# power_schematic.net
KiCad netlist of a schematic drawn in Altium Designer
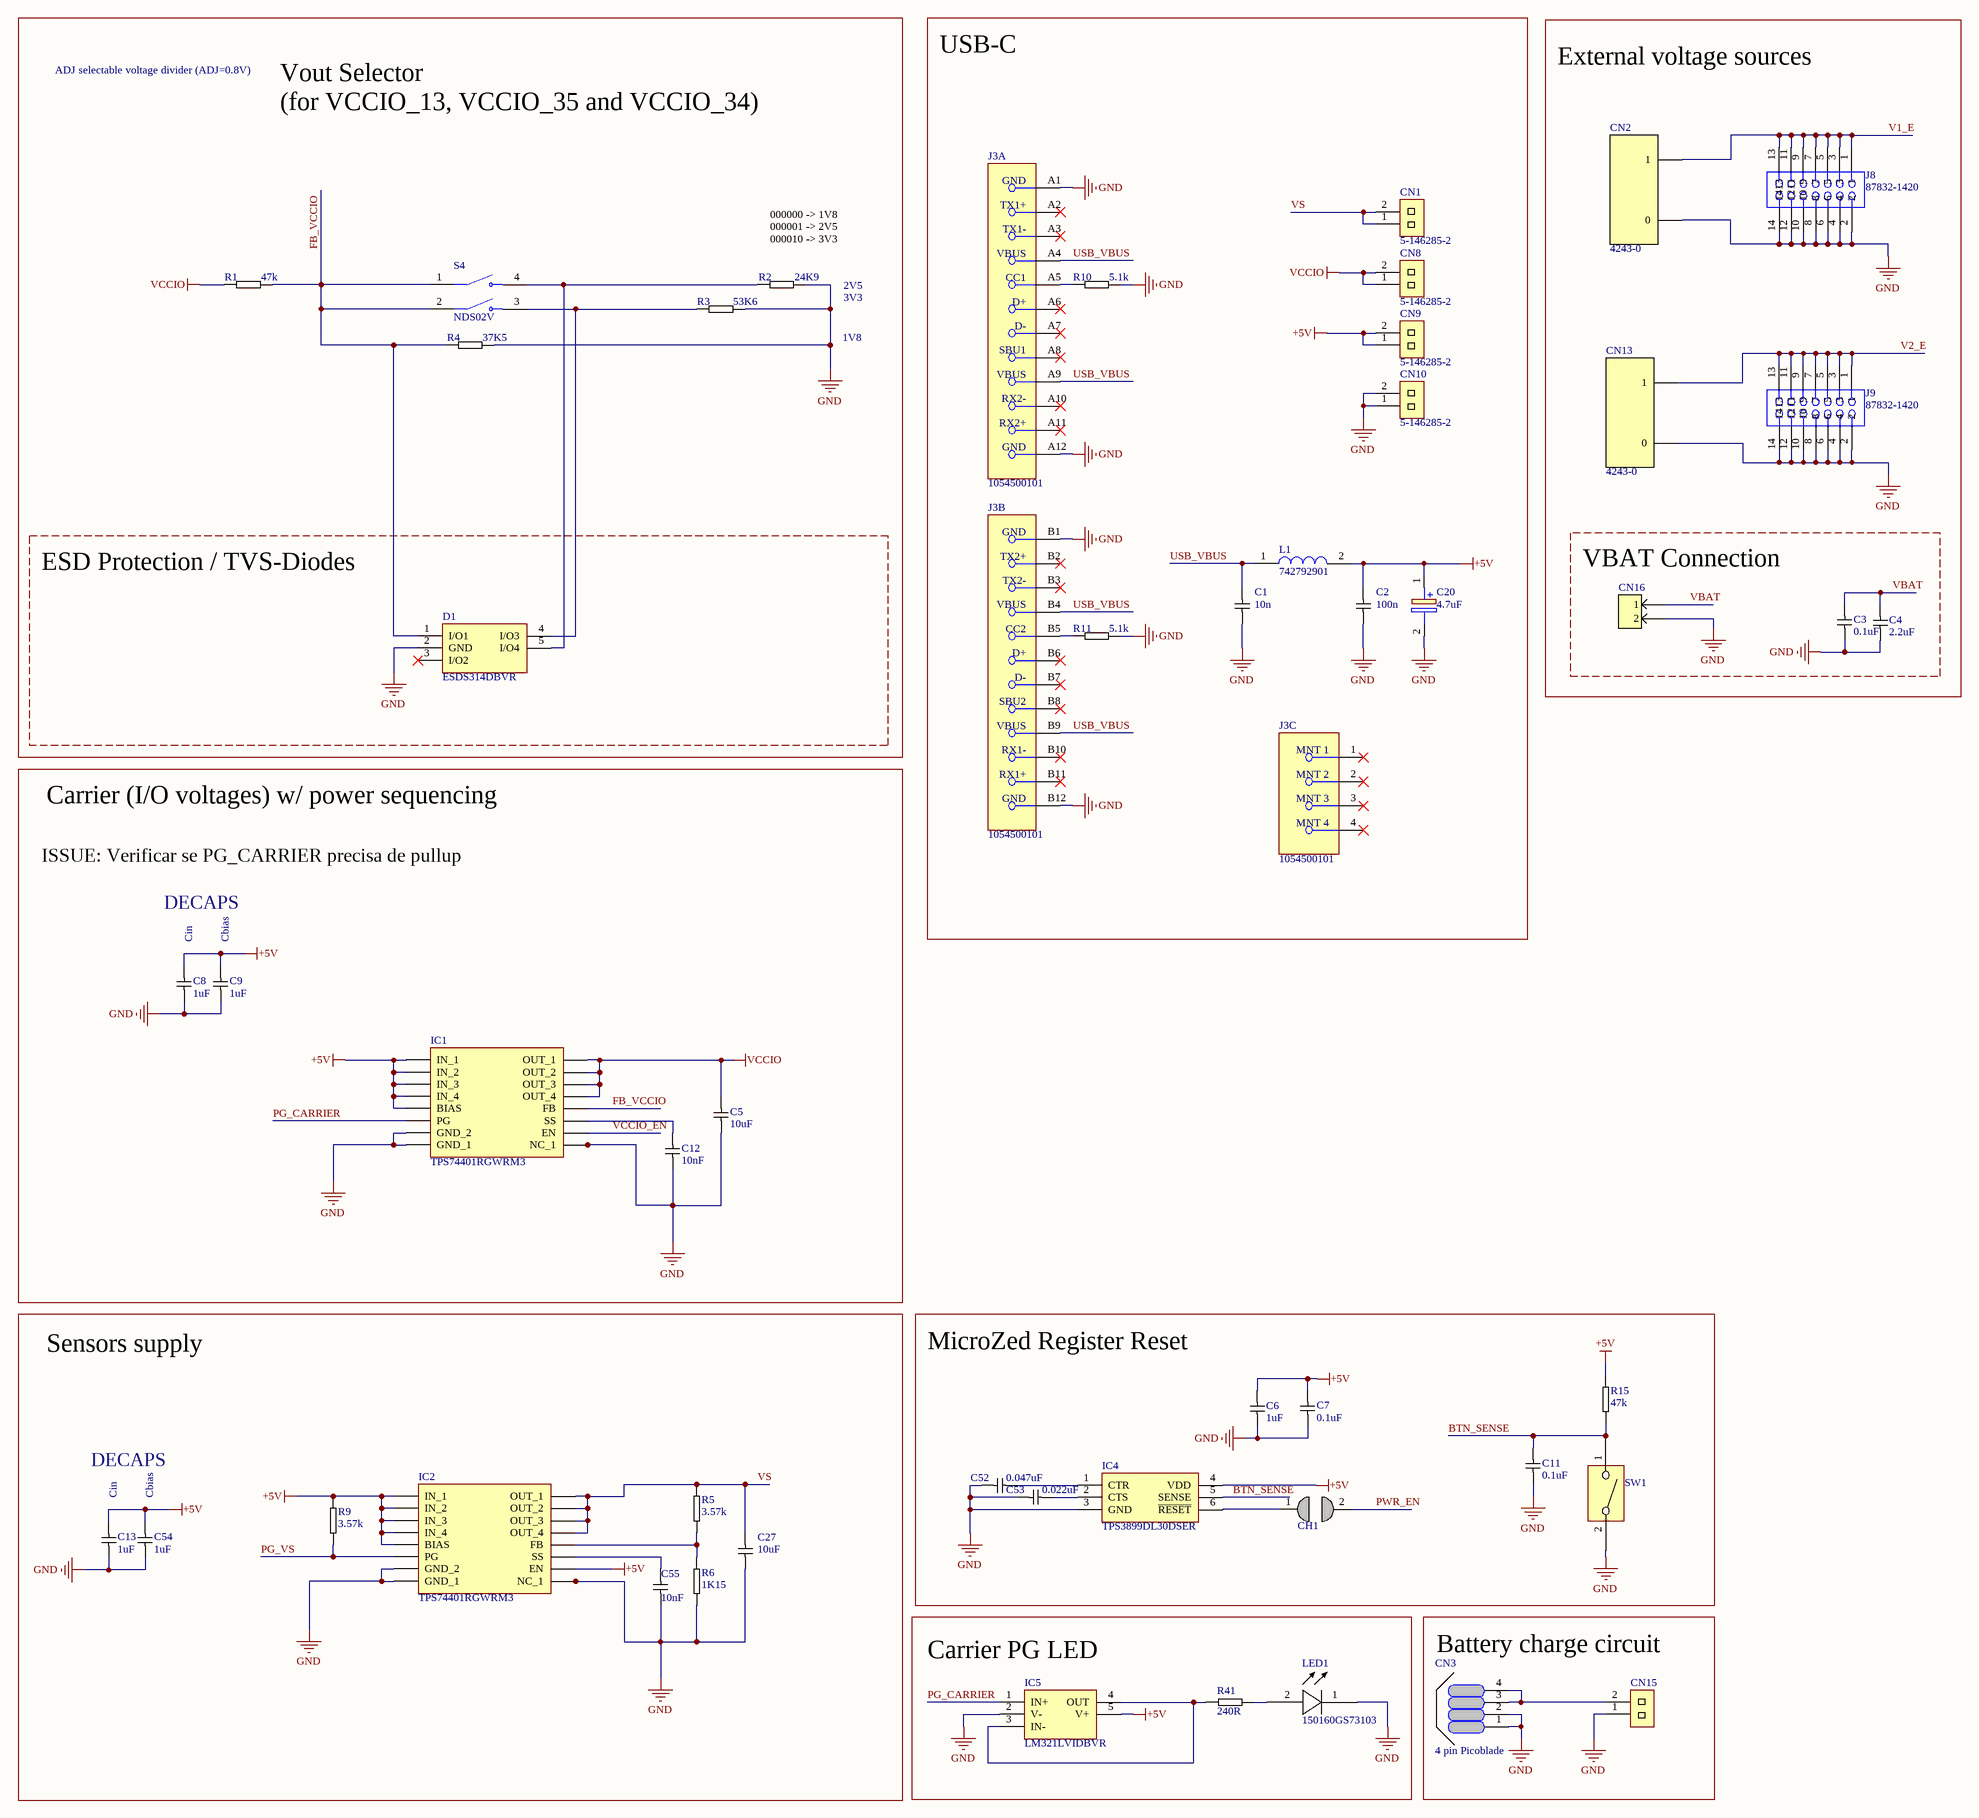
[diagram p0: power_schematic.SchDoc]

(export (version "E")
  (design (tool "Eeschema 10.0.6"))
  (components
    (comp (ref "C1")
      (value "10n")
      (footprint "C0603_MD")
      (description "CAP CER 10000PF 16V 10% X7R 0603")
      (fields (field (name "MANUFACTURER") "Murata") (field (name "VOLTAGE") "16V"))
      (libsource (lib "Capacitor") (part "GRM188R71C103KA01D"))
    )
    (comp (ref "C2")
      (value "100n")
      (footprint "C0603_MD")
      (description "CAP CER 0.1UF 25V X7R 0603")
      (fields
        (field (name "MANUFACTURER") "Samsung Electro-Mechanics America, Inc.")
        (field (name "VOLTAGE") "25V")
      )
      (libsource (lib "Capacitor") (part "CL10B104KA8NNNC"))
    )
    (comp (ref "C3")
      (value "0.1uF")
      (footprint "C0603_MD")
      (description "CAP CER 0.1UF 50V X7R 0603")
      (fields (field (name "MANUFACTURER") "Murata Electronics North America") (field (name "VOLTAGE") "50V"))
      (libsource (lib "Capacitor") (part "GRM188R71H104JA93D"))
    )
    (comp (ref "C4")
      (value "2.2uF")
      (footprint "C0603_MD")
      (description "CAP CER 2.2UF 16V X7R 0603")
      (fields (field (name "MANUFACTURER") "Taiyo Yuden") (field (name "VOLTAGE") "16V"))
      (libsource (lib "Capacitor") (part "EMK107BB7225MA-T"))
    )
    (comp (ref "C5")
      (value "10uF")
      (footprint "C0603_MD")
      (description "CAP CER 10UF 16V 20% X6S 0603")
      (fields (field (name "MANUFACTURER") "Murata Electronics North America") (field (name "VOLTAGE") "16V"))
      (libsource (lib "Capacitor") (part "GRM188C81C106MA73D"))
    )
    (comp (ref "C6")
      (value "1uF")
      (footprint "C0603_MD")
      (description "CAP CER 1UF 16V Y5V 0603")
      (fields (field (name "MANUFACTURER") "Taiyo Yuden") (field (name "VOLTAGE") "16V"))
      (libsource (lib "Capacitor") (part "EMK107F105ZA-T"))
    )
    (comp (ref "C7")
      (value "0.1uF")
      (footprint "C0603_MD")
      (description "CAP CER 0.1UF 25V X7R 0603")
      (fields
        (field (name "MANUFACTURER") "Samsung Electro-Mechanics America, Inc.")
        (field (name "VOLTAGE") "25V")
      )
      (libsource (lib "Capacitor") (part "CL10B104KA8NNNC"))
    )
    (comp (ref "C8")
      (value "Cin")
      (footprint "C0603_MD")
      (description "CAP CER 1UF 50V 10% X5R 0603")
      (fields
        (field (name "MANUFACTURER") "Taiyo Yuden")
        (field (name "VOLTAGE") "50V")
        (field (name "ALTIUM_VALUE") "1uF")
      )
      (libsource (lib "Capacitor") (part "UMK107BJ105KA-T"))
    )
    (comp (ref "C9")
      (value "Cbias")
      (footprint "C0603_MD")
      (description "CAP CER 1UF 50V 10% X5R 0603")
      (fields
        (field (name "MANUFACTURER") "Taiyo Yuden")
        (field (name "VOLTAGE") "50V")
        (field (name "ALTIUM_VALUE") "1uF")
      )
      (libsource (lib "Capacitor") (part "UMK107BJ105KA-T"))
    )
    (comp (ref "C11")
      (value "0.1uF")
      (footprint "C0603_MD")
      (description "CAP CER 0.1UF 25V X7R 0603")
      (fields
        (field (name "MANUFACTURER") "Samsung Electro-Mechanics America, Inc.")
        (field (name "VOLTAGE") "25V")
      )
      (libsource (lib "Capacitor") (part "CL10B104KA8NNNC"))
    )
    (comp (ref "C12")
      (value "10nF")
      (footprint "C0603_MD")
      (description "10000pF 50V Ceramic Capacitor X7R 0603")
      (fields
        (field (name "MANUFACTURER") "Samsung Electro-Mechanics America, Inc.")
        (field (name "VOLTAGE") "50V")
      )
      (libsource (lib "Capacitor") (part "CL10B103KB8NNNC"))
    )
    (comp (ref "C13")
      (value "Cin")
      (footprint "C0603_MD")
      (description "CAP CER 1UF 50V 10% X5R 0603")
      (fields
        (field (name "MANUFACTURER") "Taiyo Yuden")
        (field (name "VOLTAGE") "50V")
        (field (name "ALTIUM_VALUE") "1uF")
      )
      (libsource (lib "Capacitor") (part "UMK107BJ105KA-T"))
    )
    (comp (ref "C20")
      (value "4.7uF")
      (footprint "SamacSys:CAPAE660X770N")
      (description "Capacitor Polarised")
      (fields
        (field (name "MANUFACTURER_PART_NUMBER") "865080845004")
        (field (name "MOUSER PART NUMBER") "710-865080845004")
      )
      (libsource (lib "*") (part "865080845004"))
    )
    (comp (ref "C27")
      (value "10uF")
      (footprint "C0603_MD")
      (description "CAP CER 10UF 16V 20% X6S 0603")
      (fields (field (name "MANUFACTURER") "Murata Electronics North America") (field (name "VOLTAGE") "16V"))
      (libsource (lib "Capacitor") (part "GRM188C81C106MA73D"))
    )
    (comp (ref "C52")
      (value "0.047uF")
      (footprint "C0603_MD")
      (description "CAP CER 0.047UF 50V X7R 0603")
      (fields (field (name "MANUFACTURER") "Samsung Electro-Mechanics") (field (name "VOLTAGE") "50V"))
      (libsource (lib "Capacitor") (part "CL10B473KB8NNNC"))
    )
    (comp (ref "C53")
      (value "0.022uF")
      (footprint "C0603_MD")
      (description "CAP CER 0.022UF 50V X7R 0603")
      (fields
        (field (name "MANUFACTURER") "Samsung Electro-Mechanics America, Inc.")
        (field (name "VOLTAGE") "50V")
      )
      (libsource (lib "Capacitor") (part "CL10B223KB8NNNC"))
    )
    (comp (ref "C54")
      (value "Cbias")
      (footprint "C0603_MD")
      (description "CAP CER 1UF 50V 10% X5R 0603")
      (fields
        (field (name "MANUFACTURER") "Taiyo Yuden")
        (field (name "VOLTAGE") "50V")
        (field (name "ALTIUM_VALUE") "1uF")
      )
      (libsource (lib "Capacitor") (part "UMK107BJ105KA-T"))
    )
    (comp (ref "C55")
      (value "10nF")
      (footprint "C0603_MD")
      (description "10000pF 50V Ceramic Capacitor X7R 0603")
      (fields
        (field (name "MANUFACTURER") "Samsung Electro-Mechanics America, Inc.")
        (field (name "VOLTAGE") "50V")
      )
      (libsource (lib "Capacitor") (part "CL10B103KB8NNNC"))
    )
    (comp (ref "CH1")
      (value "Solder Jumper")
      (footprint "Solder Jumper")
      (description "PCB Solder jumper")
      (libsource (lib "Miscellaneous") (part "Solder Jumper"))
    )
    (comp (ref "CN1")
      (value "5-146285-2")
      (footprint "PIN BAR 2 2.54mm 180 GRAUS")
      (description "02 MODII HDR SRST B/A .100CL")
      (fields (field (name "MANUFACTURER") "TE Connectivity"))
      (libsource (lib "Connector") (part "5-146285-2"))
    )
    (comp (ref "CN2")
      (value "4243-0")
      (footprint "4243-0")
      (description "POMONA, 4243-0, Binding Post, 4243 Series, 15 A, 60 VDC, Tin Plated Contacts, Brass, Black")
      (fields (field (name "MANUFACTURER") "Pomona Electronics"))
      (libsource (lib "flatsat_platform_2") (part "4243-0"))
    )
    (comp (ref "CN3")
      (value "4 pin Picoblade")
      (footprint "PICO BLADE 0532610471")
      (description "1.25mm Pitch PicoBlade™ Header, Surface Mount, Vertical, 4 Circuits")
      (fields (field (name "MANUFACTURER") "Molex") (field (name "MANUFACTURER PART NUMBER") "53398-0471"))
      (libsource (lib "flatsat_platform_2") (part "0533980471"))
    )
    (comp (ref "CN8")
      (value "5-146285-2")
      (footprint "PIN BAR 2 2.54mm 180 GRAUS")
      (description "02 MODII HDR SRST B/A .100CL")
      (fields (field (name "MANUFACTURER") "TE Connectivity"))
      (libsource (lib "Connector") (part "5-146285-2"))
    )
    (comp (ref "CN9")
      (value "5-146285-2")
      (footprint "PIN BAR 2 2.54mm 180 GRAUS")
      (description "02 MODII HDR SRST B/A .100CL")
      (fields (field (name "MANUFACTURER") "TE Connectivity"))
      (libsource (lib "Connector") (part "5-146285-2"))
    )
    (comp (ref "CN10")
      (value "5-146285-2")
      (footprint "PIN BAR 2 2.54mm 180 GRAUS")
      (description "02 MODII HDR SRST B/A .100CL")
      (fields (field (name "MANUFACTURER") "TE Connectivity"))
      (libsource (lib "Connector") (part "5-146285-2"))
    )
    (comp (ref "CN13")
      (value "4243-0")
      (footprint "4243-0")
      (description "POMONA, 4243-0, Binding Post, 4243 Series, 15 A, 60 VDC, Tin Plated Contacts, Brass, Black")
      (fields (field (name "MANUFACTURER") "Pomona Electronics"))
      (libsource (lib "flatsat_platform_2") (part "4243-0"))
    )
    (comp (ref "CN15")
      (value "JST 2 position header 2.5mm")
      (footprint "B2B-XH-A-M(LF)(SN)")
      (description "CONN HEADER TOP 2POS 2.5MM GRN")
      (fields (field (name "MANUFACTURER") "TE Connectivity"))
      (libsource (lib "Connector") (part "5-146285-2"))
    )
    (comp (ref "CN16")
      (value "JST 2 position header 2.5mm")
      (footprint "B2B-XH-A-M(LF)(SN)")
      (description "CONN HEADER TOP 2POS 2.5MM GRN")
      (fields
        (field (name "MANUFACTURER") "JST")
        (field (name "MANUFACTURER PART NUMBER") "B2B-XH-A-M(LF)(SN)")
      )
      (libsource (lib "flatsat_platform_2") (part "B2B-XH-A-M(LF)(SN)"))
    )
    (comp (ref "D1")
      (value "ESDS314DBVR")
      (footprint "flatsat_platform_2:SOT95P280X145-5N")
      (description "Diode")
      (fields (field (name "MOUSER PART NUMBER") "595-ESDS314DBVR"))
      (libsource (lib "*") (part "ESDS314DBVR"))
    )
    (comp (ref "IC1")
      (value "TPS74401RGWRM3")
      (footprint "SamacSys:QFN65P500X500X100-21N-D")
      (description "Integrated Circuit")
      (fields (field (name "MOUSER PART NUMBER") "595-TPS74401RGWRM3"))
      (libsource (lib "SamacSys") (part "TPS74401RGWRM3"))
    )
    (comp (ref "IC2")
      (value "TPS74401RGWRM3")
      (footprint "SamacSys:QFN65P500X500X100-21N-D")
      (description "Integrated Circuit")
      (fields (field (name "MOUSER PART NUMBER") "595-TPS74401RGWRM3"))
      (libsource (lib "SamacSys") (part "TPS74401RGWRM3"))
    )
    (comp (ref "IC4")
      (value "TPS3899DL30DSER")
      (footprint "flatsat_platform_2:TPS3899DL30DSER")
      (description "Integrated Circuit")
      (fields (field (name "MOUSER PART NUMBER") "595-TPS3899DL30DSER"))
      (libsource (lib "*") (part "TPS3899DL30DSER"))
    )
    (comp (ref "IC5")
      (value "LM321LVIDBVR")
      (footprint "flatsat_platform_2:SOT95P280X145-5N")
      (description "Integrated Circuit")
      (fields (field (name "MOUSER PART NUMBER") "595-LM321LVIDBVR"))
      (libsource (lib "*") (part "LM321LVIDBVR"))
    )
    (comp (ref "J3")
      (value "1054500101")
      (footprint "FP-1054500101-MFG")
      (description "CONN RCP USB3.1 TYPEC 24P SMD RA")
      (fields
        (field (name "MANUFACTURER") "Molex")
        (field (name "OCTOPART") "https://octopart.com/105450-0101-molex-68082325")
      )
      (libsource (lib "Altium Content Vault") (part "9808b19ecaf079fb99eed69f0495cd0"))
    )
    (comp (ref "J8")
      (value "87832-1420")
      (footprint "SAMTEC_TSW-107-05-F-D")
      (description "Connector Header Surface Mount 14 position 0.079 _2.00mm_")
      (fields (field (name "MF") "Molex") (field (name "MANUFACTURER PART NUMBER") "TSW-107-05-F-D"))
      (libsource (lib "flatsat_platform_2") (part "87832-1420"))
    )
    (comp (ref "J9")
      (value "87832-1420")
      (footprint "SAMTEC_TSW-107-05-F-D")
      (description "Connector Header Surface Mount 14 position 0.079 _2.00mm_")
      (fields (field (name "MF") "Molex") (field (name "MANUFACTURER PART NUMBER") "TSW-107-05-F-D"))
      (libsource (lib "flatsat_platform_2") (part "87832-1420"))
    )
    (comp (ref "L1")
      (value "742792901")
      (footprint "SamacSys:WE-PF_7427929...60")
      (description "Inductor")
      (fields (field (name "MOUSER PART NUMBER") "710-742792901"))
      (libsource (lib "SamacSys") (part "742792901"))
    )
    (comp (ref "LED1")
      (value "150160GS73103")
      (footprint "0603 (1608 metric)")
      (libsource (lib "flatsat_platform_2") (part "150160GS73103"))
    )
    (comp (ref "R1")
      (value "47k")
      (footprint "R0603_HD")
      (description "RES 47K OHM 1/10W 1% 0603")
      (fields (field (name "MANUFACTURER") "Stackpole Electronics Inc") (field (name "TOLERANCE") "1%"))
      (libsource (lib "Resistor") (part "RMCF0603FT47K0"))
    )
    (comp (ref "R2")
      (value "24K9")
      (footprint "R0603_HD")
      (description "Resistor")
      (fields
        (field (name "MANUFACTURER_PART_NUMBER") "ERJ-PB3B2492V")
        (field (name "MOUSER PART NUMBER") "667-ERJ-PB3B2492V")
      )
      (libsource (lib "SamacSys") (part "ERJ-PB3B2492V"))
    )
    (comp (ref "R3")
      (value "53K6")
      (footprint "R0603_HD")
      (description "Resistor")
      (fields (field (name "MANUFACTURER_PART_NUMBER") "ERJH3ED3652V"))
      (libsource (lib "SamacSys") (part "ERJH3ED3652V"))
    )
    (comp (ref "R4")
      (value "37K5")
      (footprint "R0603_HD")
      (description "Resistor")
      (fields (field (name "MANUFACTURER_PART_NUMBER") "ERJ-H3ED3652V"))
      (libsource (lib "SamacSys") (part "ERJ-H3ED3652V"))
    )
    (comp (ref "R5")
      (value "3.57k")
      (footprint "R0603_MD")
      (description "RES 3.57K OHM 1/10W 1% 0603")
      (fields (field (name "MANUFACTURER") "Stackpole Electronics Inc") (field (name "TOLERANCE") "1%"))
      (libsource (lib "Resistor") (part "RMCF0603FT3K57"))
    )
    (comp (ref "R6")
      (value "1K15")
      (footprint "R0603_MD")
      (description "Resistor")
      (fields
        (field (name "MANUFACTURER_PART_NUMBER") "CPF0603F1K15C1")
        (field (name "MOUSER PART NUMBER") "279-CPF0603F1K15C1")
      )
      (libsource (lib "SamacSys") (part "CPF0603F1K15C1"))
    )
    (comp (ref "R9")
      (value "3.57k")
      (footprint "R0603_MD")
      (description "RES 3.57K OHM 1/10W 1% 0603")
      (fields (field (name "MANUFACTURER") "Stackpole Electronics Inc") (field (name "TOLERANCE") "1%"))
      (libsource (lib "Resistor") (part "RMCF0603FT3K57"))
    )
    (comp (ref "R10")
      (value "5.1k")
      (footprint "R0603_MD")
      (description "RES 5.1K OHM 1/10W 1% 0603")
      (fields (field (name "MANUFACTURER") "Stackpole Electronics Inc") (field (name "TOLERANCE") "1%"))
      (libsource (lib "Resistor") (part "RMCF0603FT5K10"))
    )
    (comp (ref "R11")
      (value "5.1k")
      (footprint "R0603_MD")
      (description "RES 5.1K OHM 1/10W 1% 0603")
      (fields (field (name "MANUFACTURER") "Stackpole Electronics Inc") (field (name "TOLERANCE") "1%"))
      (libsource (lib "Resistor") (part "RMCF0603FT5K10"))
    )
    (comp (ref "R15")
      (value "47k")
      (footprint "R0603_MD")
      (description "RES 47K OHM 1/10W 1% 0603")
      (fields (field (name "MANUFACTURER") "Stackpole Electronics Inc") (field (name "TOLERANCE") "1%"))
      (libsource (lib "Resistor") (part "RMCF0603FT47K0"))
    )
    (comp (ref "R41")
      (value "240R")
      (footprint "R0603_MD")
      (description "RES SMD 240 OHM 1% 1/10W 0603")
      (fields (field (name "MANUFACTURER") "Yageo") (field (name "TOLERANCE") "1%"))
      (libsource (lib "Resistor") (part "RC0603FR-07240RL"))
    )
    (comp (ref "S4")
      (value "NDS02V")
      (footprint "SamacSys:NDS02V")
      (description "Switch")
      (fields (field (name "MOUSER PART NUMBER") "642-NDS02V"))
      (libsource (lib "SamacSys") (part "NDS02V"))
    )
    (comp (ref "SW1")
      (value "434123050836")
      (footprint "4341x30508x6")
      (description "SWITCH TACTILE SPST-NO 0.05A 12V")
      (fields (field (name "MANUFACTURER") "Wurth Electronics Inc."))
      (libsource (lib "Switch") (part "434123050836"))
    )
  )
  (nets
    (net (code "1") (name "+5V") (class "Default")
      (node (ref "C13") (pin "1") (pinfunction "1_1") (pintype "passive"))
      (node (ref "C2") (pin "1") (pinfunction "1_1") (pintype "passive"))
      (node (ref "C20") (pin "1") (pinfunction "+_1") (pintype "passive"))
      (node (ref "C54") (pin "1") (pinfunction "1_1") (pintype "passive"))
      (node (ref "C6") (pin "1") (pinfunction "1_1") (pintype "passive"))
      (node (ref "C7") (pin "1") (pinfunction "1_1") (pintype "passive"))
      (node (ref "C8") (pin "1") (pinfunction "1_1") (pintype "passive"))
      (node (ref "C9") (pin "1") (pinfunction "1_1") (pintype "passive"))
      (node (ref "CN9") (pin "1") (pinfunction "1_1") (pintype "passive"))
      (node (ref "CN9") (pin "2") (pinfunction "2_2") (pintype "passive"))
      (node (ref "IC1") (pin "10") (pinfunction "BIAS_10") (pintype "passive"))
      (node (ref "IC1") (pin "5") (pinfunction "IN_1_5") (pintype "passive"))
      (node (ref "IC1") (pin "6") (pinfunction "IN_2_6") (pintype "passive"))
      (node (ref "IC1") (pin "7") (pinfunction "IN_3_7") (pintype "passive"))
      (node (ref "IC1") (pin "8") (pinfunction "IN_4_8") (pintype "passive"))
      (node (ref "IC2") (pin "10") (pinfunction "BIAS_10") (pintype "passive"))
      (node (ref "IC2") (pin "11") (pinfunction "EN_11") (pintype "passive"))
      (node (ref "IC2") (pin "5") (pinfunction "IN_1_5") (pintype "passive"))
      (node (ref "IC2") (pin "6") (pinfunction "IN_2_6") (pintype "passive"))
      (node (ref "IC2") (pin "7") (pinfunction "IN_3_7") (pintype "passive"))
      (node (ref "IC2") (pin "8") (pinfunction "IN_4_8") (pintype "passive"))
      (node (ref "IC4") (pin "4") (pinfunction "VDD_4") (pintype "passive"))
      (node (ref "IC5") (pin "5") (pinfunction "V+_5") (pintype "passive"))
      (node (ref "L1") (pin "2") (pinfunction "2_2") (pintype "passive"))
      (node (ref "R15") (pin "1") (pinfunction "1_1") (pintype "passive"))
      (node (ref "R9") (pin "1") (pinfunction "1_1") (pintype "passive"))
    )
    (net (code "2") (name "/BTN_SENSE") (class "Default")
      (node (ref "C11") (pin "2") (pinfunction "2_2") (pintype "passive"))
      (node (ref "IC4") (pin "5") (pinfunction "SENSE_5") (pintype "passive"))
      (node (ref "R15") (pin "2") (pinfunction "2_2") (pintype "passive"))
      (node (ref "SW1") (pin "1") (pinfunction "NC_1") (pintype "passive"))
    )
    (net (code "3") (name "/FB_VCCIO") (class "Default")
      (node (ref "D1") (pin "1") (pinfunction "I/O1_1") (pintype "passive"))
      (node (ref "IC1") (pin "16") (pinfunction "FB_16") (pintype "passive"))
      (node (ref "R1") (pin "2") (pinfunction "2_2") (pintype "passive"))
      (node (ref "R4") (pin "1") (pinfunction "1_1") (pintype "passive"))
      (node (ref "S4") (pin "1") (pinfunction "COM_1_1") (pintype "passive"))
      (node (ref "S4") (pin "2") (pinfunction "COM_2_2") (pintype "passive"))
    )
    (net (code "4") (name "/PG_CARRIER") (class "Default")
      (node (ref "IC1") (pin "9") (pinfunction "PG_9") (pintype "passive"))
      (node (ref "IC5") (pin "1") (pinfunction "IN+_1") (pintype "passive"))
    )
    (net (code "5") (name "/PG_VS") (class "Default")
      (node (ref "IC2") (pin "9") (pinfunction "PG_9") (pintype "passive"))
      (node (ref "R9") (pin "2") (pinfunction "2_2") (pintype "passive"))
    )
    (net (code "6") (name "/PWR_EN") (class "Default")
      (node (ref "CH1") (pin "2") (pinfunction "C_2") (pintype "passive"))
    )
    (net (code "7") (name "/USB_VBUS") (class "Default")
      (node (ref "C1") (pin "1") (pinfunction "1_1") (pintype "passive"))
      (node (ref "J3") (pin "A4") (pinfunction "VBUS_A4") (pintype "passive"))
      (node (ref "J3") (pin "A9") (pinfunction "VBUS_A9") (pintype "passive"))
      (node (ref "J3") (pin "B4") (pinfunction "VBUS_B4") (pintype "passive"))
      (node (ref "J3") (pin "B9") (pinfunction "VBUS_B9") (pintype "passive"))
      (node (ref "L1") (pin "1") (pinfunction "1_1") (pintype "passive"))
    )
    (net (code "8") (name "/V1_E") (class "Default")
      (node (ref "CN2") (pin "1") (pinfunction "1_1") (pintype "passive"))
      (node (ref "J8") (pin "1") (pinfunction "1_1") (pintype "passive"))
      (node (ref "J8") (pin "11") (pinfunction "11_11") (pintype "passive"))
      (node (ref "J8") (pin "13") (pinfunction "13_13") (pintype "passive"))
      (node (ref "J8") (pin "3") (pinfunction "3_3") (pintype "passive"))
      (node (ref "J8") (pin "5") (pinfunction "5_5") (pintype "passive"))
      (node (ref "J8") (pin "7") (pinfunction "7_7") (pintype "passive"))
      (node (ref "J8") (pin "9") (pinfunction "9_9") (pintype "passive"))
    )
    (net (code "9") (name "/V2_E") (class "Default")
      (node (ref "CN13") (pin "1") (pinfunction "1_1") (pintype "passive"))
      (node (ref "J9") (pin "1") (pinfunction "1_1") (pintype "passive"))
      (node (ref "J9") (pin "11") (pinfunction "11_11") (pintype "passive"))
      (node (ref "J9") (pin "13") (pinfunction "13_13") (pintype "passive"))
      (node (ref "J9") (pin "3") (pinfunction "3_3") (pintype "passive"))
      (node (ref "J9") (pin "5") (pinfunction "5_5") (pintype "passive"))
      (node (ref "J9") (pin "7") (pinfunction "7_7") (pintype "passive"))
      (node (ref "J9") (pin "9") (pinfunction "9_9") (pintype "passive"))
    )
    (net (code "10") (name "/VBAT") (class "Default")
      (node (ref "C3") (pin "1") (pinfunction "1_1") (pintype "passive"))
      (node (ref "C4") (pin "1") (pinfunction "1_1") (pintype "passive"))
      (node (ref "CN16") (pin "1") (pinfunction "1_1") (pintype "passive"))
    )
    (net (code "11") (name "/VCCIO_EN") (class "Default")
      (node (ref "IC1") (pin "11") (pinfunction "EN_11") (pintype "passive"))
    )
    (net (code "12") (name "/VS") (class "Default")
      (node (ref "C27") (pin "1") (pinfunction "1_1") (pintype "passive"))
      (node (ref "CN1") (pin "1") (pinfunction "1_1") (pintype "passive"))
      (node (ref "CN1") (pin "2") (pinfunction "2_2") (pintype "passive"))
      (node (ref "IC2") (pin "1") (pinfunction "OUT_1_1") (pintype "passive"))
      (node (ref "IC2") (pin "18") (pinfunction "OUT_2_18") (pintype "passive"))
      (node (ref "IC2") (pin "19") (pinfunction "OUT_3_19") (pintype "passive"))
      (node (ref "IC2") (pin "20") (pinfunction "OUT_4_20") (pintype "passive"))
      (node (ref "R5") (pin "1") (pinfunction "1_1") (pintype "passive"))
    )
    (net (code "13") (name "GND") (class "Default")
      (node (ref "C1") (pin "2") (pinfunction "2_2") (pintype "passive"))
      (node (ref "C11") (pin "1") (pinfunction "1_1") (pintype "passive"))
      (node (ref "C12") (pin "2") (pinfunction "2_2") (pintype "passive"))
      (node (ref "C13") (pin "2") (pinfunction "2_2") (pintype "passive"))
      (node (ref "C2") (pin "2") (pinfunction "2_2") (pintype "passive"))
      (node (ref "C20") (pin "2") (pinfunction "-_2") (pintype "passive"))
      (node (ref "C27") (pin "2") (pinfunction "2_2") (pintype "passive"))
      (node (ref "C3") (pin "2") (pinfunction "2_2") (pintype "passive"))
      (node (ref "C4") (pin "2") (pinfunction "2_2") (pintype "passive"))
      (node (ref "C5") (pin "2") (pinfunction "2_2") (pintype "passive"))
      (node (ref "C52") (pin "2") (pinfunction "2_2") (pintype "passive"))
      (node (ref "C53") (pin "2") (pinfunction "2_2") (pintype "passive"))
      (node (ref "C54") (pin "2") (pinfunction "2_2") (pintype "passive"))
      (node (ref "C55") (pin "1") (pinfunction "1_1") (pintype "passive"))
      (node (ref "C6") (pin "2") (pinfunction "2_2") (pintype "passive"))
      (node (ref "C7") (pin "2") (pinfunction "2_2") (pintype "passive"))
      (node (ref "C8") (pin "2") (pinfunction "2_2") (pintype "passive"))
      (node (ref "C9") (pin "2") (pinfunction "2_2") (pintype "passive"))
      (node (ref "CN10") (pin "1") (pinfunction "1_1") (pintype "passive"))
      (node (ref "CN10") (pin "2") (pinfunction "2_2") (pintype "passive"))
      (node (ref "CN13") (pin "0") (pinfunction "0_0") (pintype "passive"))
      (node (ref "CN15") (pin "1") (pinfunction "1_1") (pintype "passive"))
      (node (ref "CN16") (pin "2") (pinfunction "2_2") (pintype "passive"))
      (node (ref "CN2") (pin "0") (pinfunction "0_0") (pintype "passive"))
      (node (ref "CN3") (pin "1") (pinfunction "1_1") (pintype "passive"))
      (node (ref "CN3") (pin "2") (pinfunction "2_2") (pintype "passive"))
      (node (ref "D1") (pin "2") (pinfunction "GND_2") (pintype "passive"))
      (node (ref "IC1") (pin "12") (pinfunction "GND_1_12") (pintype "passive"))
      (node (ref "IC1") (pin "13") (pinfunction "NC_4_13") (pintype "passive"))
      (node (ref "IC1") (pin "14") (pinfunction "NC_5_14") (pintype "passive"))
      (node (ref "IC1") (pin "17") (pinfunction "NC_6_17") (pintype "passive"))
      (node (ref "IC1") (pin "2") (pinfunction "NC_1_2") (pintype "passive"))
      (node (ref "IC1") (pin "21") (pinfunction "GND_2_21") (pintype "passive"))
      (node (ref "IC1") (pin "3") (pinfunction "NC_2_3") (pintype "passive"))
      (node (ref "IC1") (pin "4") (pinfunction "NC_3_4") (pintype "passive"))
      (node (ref "IC2") (pin "12") (pinfunction "GND_1_12") (pintype "passive"))
      (node (ref "IC2") (pin "13") (pinfunction "NC_4_13") (pintype "passive"))
      (node (ref "IC2") (pin "14") (pinfunction "NC_5_14") (pintype "passive"))
      (node (ref "IC2") (pin "17") (pinfunction "NC_6_17") (pintype "passive"))
      (node (ref "IC2") (pin "2") (pinfunction "NC_1_2") (pintype "passive"))
      (node (ref "IC2") (pin "21") (pinfunction "GND_2_21") (pintype "passive"))
      (node (ref "IC2") (pin "3") (pinfunction "NC_2_3") (pintype "passive"))
      (node (ref "IC2") (pin "4") (pinfunction "NC_3_4") (pintype "passive"))
      (node (ref "IC4") (pin "3") (pinfunction "GND_3") (pintype "passive"))
      (node (ref "IC5") (pin "2") (pinfunction "V-_2") (pintype "passive"))
      (node (ref "J3") (pin "A1") (pinfunction "GND_A1") (pintype "passive"))
      (node (ref "J3") (pin "A12") (pinfunction "GND_A12") (pintype "passive"))
      (node (ref "J3") (pin "B1") (pinfunction "GND_B1") (pintype "passive"))
      (node (ref "J3") (pin "B12") (pinfunction "GND_B12") (pintype "passive"))
      (node (ref "J8") (pin "10") (pinfunction "10_10") (pintype "passive"))
      (node (ref "J8") (pin "12") (pinfunction "12_12") (pintype "passive"))
      (node (ref "J8") (pin "14") (pinfunction "14_14") (pintype "passive"))
      (node (ref "J8") (pin "2") (pinfunction "2_2") (pintype "passive"))
      (node (ref "J8") (pin "4") (pinfunction "4_4") (pintype "passive"))
      (node (ref "J8") (pin "6") (pinfunction "6_6") (pintype "passive"))
      (node (ref "J8") (pin "8") (pinfunction "8_8") (pintype "passive"))
      (node (ref "J9") (pin "10") (pinfunction "10_10") (pintype "passive"))
      (node (ref "J9") (pin "12") (pinfunction "12_12") (pintype "passive"))
      (node (ref "J9") (pin "14") (pinfunction "14_14") (pintype "passive"))
      (node (ref "J9") (pin "2") (pinfunction "2_2") (pintype "passive"))
      (node (ref "J9") (pin "4") (pinfunction "4_4") (pintype "passive"))
      (node (ref "J9") (pin "6") (pinfunction "6_6") (pintype "passive"))
      (node (ref "J9") (pin "8") (pinfunction "8_8") (pintype "passive"))
      (node (ref "LED1") (pin "1") (pinfunction "Cathode_1") (pintype "passive"))
      (node (ref "R10") (pin "2") (pinfunction "2_2") (pintype "passive"))
      (node (ref "R11") (pin "2") (pinfunction "2_2") (pintype "passive"))
      (node (ref "R2") (pin "2") (pinfunction "2_2") (pintype "passive"))
      (node (ref "R3") (pin "2") (pinfunction "2_2") (pintype "passive"))
      (node (ref "R4") (pin "2") (pinfunction "2_2") (pintype "passive"))
      (node (ref "R6") (pin "2") (pinfunction "2_2") (pintype "passive"))
      (node (ref "SW1") (pin "2") (pinfunction "C_2") (pintype "passive"))
    )
    (net (code "14") (name "Net-(CH1-NC)") (class "Default")
      (node (ref "CH1") (pin "1") (pinfunction "NC_1") (pintype "passive"))
      (node (ref "IC4") (pin "6") (pinfunction "~{RESET}_6") (pintype "passive"))
    )
    (net (code "15") (name "Net-(CN15-Pad2)") (class "Default")
      (node (ref "CN15") (pin "2") (pinfunction "2_2") (pintype "passive"))
      (node (ref "CN3") (pin "3") (pinfunction "3_3") (pintype "passive"))
      (node (ref "CN3") (pin "4") (pinfunction "4_4") (pintype "passive"))
    )
    (net (code "16") (name "Net-(D1-I{slash}O3)") (class "Default")
      (node (ref "D1") (pin "4") (pinfunction "I/O3_4") (pintype "passive"))
      (node (ref "R3") (pin "1") (pinfunction "1_1") (pintype "passive"))
      (node (ref "S4") (pin "3") (pinfunction "NO_1_3") (pintype "passive"))
    )
    (net (code "17") (name "Net-(D1-I{slash}O4)") (class "Default")
      (node (ref "D1") (pin "5") (pinfunction "I/O4_5") (pintype "passive"))
      (node (ref "R2") (pin "1") (pinfunction "1_1") (pintype "passive"))
      (node (ref "S4") (pin "4") (pinfunction "NO_2_4") (pintype "passive"))
    )
    (net (code "18") (name "Net-(IC1-SS)") (class "Default")
      (node (ref "C12") (pin "1") (pinfunction "1_1") (pintype "passive"))
      (node (ref "IC1") (pin "15") (pinfunction "SS_15") (pintype "passive"))
    )
    (net (code "19") (name "Net-(IC2-FB)") (class "Default")
      (node (ref "IC2") (pin "16") (pinfunction "FB_16") (pintype "passive"))
      (node (ref "R5") (pin "2") (pinfunction "2_2") (pintype "passive"))
      (node (ref "R6") (pin "1") (pinfunction "1_1") (pintype "passive"))
    )
    (net (code "20") (name "Net-(IC2-SS)") (class "Default")
      (node (ref "C55") (pin "2") (pinfunction "2_2") (pintype "passive"))
      (node (ref "IC2") (pin "15") (pinfunction "SS_15") (pintype "passive"))
    )
    (net (code "21") (name "Net-(IC4-CTR)") (class "Default")
      (node (ref "C52") (pin "1") (pinfunction "1_1") (pintype "passive"))
      (node (ref "IC4") (pin "1") (pinfunction "CTR_1") (pintype "passive"))
    )
    (net (code "22") (name "Net-(IC4-CTS)") (class "Default")
      (node (ref "C53") (pin "1") (pinfunction "1_1") (pintype "passive"))
      (node (ref "IC4") (pin "2") (pinfunction "CTS_2") (pintype "passive"))
    )
    (net (code "23") (name "Net-(IC5-IN-)") (class "Default")
      (node (ref "IC5") (pin "3") (pinfunction "IN-_3") (pintype "passive"))
      (node (ref "IC5") (pin "4") (pinfunction "OUT_4") (pintype "passive"))
      (node (ref "R41") (pin "1") (pinfunction "1_1") (pintype "passive"))
    )
    (net (code "24") (name "Net-(J3A-CC1)") (class "Default")
      (node (ref "J3") (pin "A5") (pinfunction "CC1_A5") (pintype "passive"))
      (node (ref "R10") (pin "1") (pinfunction "1_1") (pintype "passive"))
    )
    (net (code "25") (name "Net-(J3B-CC2)") (class "Default")
      (node (ref "J3") (pin "B5") (pinfunction "CC2_B5") (pintype "passive"))
      (node (ref "R11") (pin "1") (pinfunction "1_1") (pintype "passive"))
    )
    (net (code "26") (name "Net-(LED1-anode)") (class "Default")
      (node (ref "LED1") (pin "2") (pinfunction "anode_2") (pintype "passive"))
      (node (ref "R41") (pin "2") (pinfunction "2_2") (pintype "passive"))
    )
    (net (code "27") (name "VCCIO") (class "Default")
      (node (ref "C5") (pin "1") (pinfunction "1_1") (pintype "passive"))
      (node (ref "CN8") (pin "1") (pinfunction "1_1") (pintype "passive"))
      (node (ref "CN8") (pin "2") (pinfunction "2_2") (pintype "passive"))
      (node (ref "IC1") (pin "1") (pinfunction "OUT_1_1") (pintype "passive"))
      (node (ref "IC1") (pin "18") (pinfunction "OUT_2_18") (pintype "passive"))
      (node (ref "IC1") (pin "19") (pinfunction "OUT_3_19") (pintype "passive"))
      (node (ref "IC1") (pin "20") (pinfunction "OUT_4_20") (pintype "passive"))
      (node (ref "R1") (pin "1") (pinfunction "1_1") (pintype "passive"))
    )
    (net (code "28") (name "unconnected-(D1-I{slash}O2-Pad3)") (class "Default")
      (node (ref "D1") (pin "3") (pinfunction "I/O2_3") (pintype "passive+no_connect"))
    )
    (net (code "29") (name "unconnected-(J3A-D+-PadA6)") (class "Default")
      (node (ref "J3") (pin "A6") (pinfunction "D+_A6") (pintype "passive+no_connect"))
    )
    (net (code "30") (name "unconnected-(J3A-D--PadA7)") (class "Default")
      (node (ref "J3") (pin "A7") (pinfunction "D-_A7") (pintype "passive+no_connect"))
    )
    (net (code "31") (name "unconnected-(J3A-RX2+-PadA11)") (class "Default")
      (node (ref "J3") (pin "A11") (pinfunction "RX2+_A11") (pintype "passive+no_connect"))
    )
    (net (code "32") (name "unconnected-(J3A-RX2--PadA10)") (class "Default")
      (node (ref "J3") (pin "A10") (pinfunction "RX2-_A10") (pintype "passive+no_connect"))
    )
    (net (code "33") (name "unconnected-(J3A-SBU1-PadA8)") (class "Default")
      (node (ref "J3") (pin "A8") (pinfunction "SBU1_A8") (pintype "passive+no_connect"))
    )
    (net (code "34") (name "unconnected-(J3A-TX1+-PadA2)") (class "Default")
      (node (ref "J3") (pin "A2") (pinfunction "TX1+_A2") (pintype "passive+no_connect"))
    )
    (net (code "35") (name "unconnected-(J3A-TX1--PadA3)") (class "Default")
      (node (ref "J3") (pin "A3") (pinfunction "TX1-_A3") (pintype "passive+no_connect"))
    )
    (net (code "36") (name "unconnected-(J3B-D+-PadB6)") (class "Default")
      (node (ref "J3") (pin "B6") (pinfunction "D+_B6") (pintype "passive+no_connect"))
    )
    (net (code "37") (name "unconnected-(J3B-D--PadB7)") (class "Default")
      (node (ref "J3") (pin "B7") (pinfunction "D-_B7") (pintype "passive+no_connect"))
    )
    (net (code "38") (name "unconnected-(J3B-RX1+-PadB11)") (class "Default")
      (node (ref "J3") (pin "B11") (pinfunction "RX1+_B11") (pintype "passive+no_connect"))
    )
    (net (code "39") (name "unconnected-(J3B-RX1--PadB10)") (class "Default")
      (node (ref "J3") (pin "B10") (pinfunction "RX1-_B10") (pintype "passive+no_connect"))
    )
    (net (code "40") (name "unconnected-(J3B-SBU2-PadB8)") (class "Default")
      (node (ref "J3") (pin "B8") (pinfunction "SBU2_B8") (pintype "passive+no_connect"))
    )
    (net (code "41") (name "unconnected-(J3B-TX2+-PadB2)") (class "Default")
      (node (ref "J3") (pin "B2") (pinfunction "TX2+_B2") (pintype "passive+no_connect"))
    )
    (net (code "42") (name "unconnected-(J3B-TX2--PadB3)") (class "Default")
      (node (ref "J3") (pin "B3") (pinfunction "TX2-_B3") (pintype "passive+no_connect"))
    )
    (net (code "43") (name "unconnected-(J3C-MNT_1-Pad1)") (class "Default")
      (node (ref "J3") (pin "1") (pinfunction "MNT_1_1") (pintype "passive+no_connect"))
    )
    (net (code "44") (name "unconnected-(J3C-MNT_2-Pad2)") (class "Default")
      (node (ref "J3") (pin "2") (pinfunction "MNT_2_2") (pintype "passive+no_connect"))
    )
    (net (code "45") (name "unconnected-(J3C-MNT_3-Pad3)") (class "Default")
      (node (ref "J3") (pin "3") (pinfunction "MNT_3_3") (pintype "passive+no_connect"))
    )
    (net (code "46") (name "unconnected-(J3C-MNT_4-Pad4)") (class "Default")
      (node (ref "J3") (pin "4") (pinfunction "MNT_4_4") (pintype "passive+no_connect"))
    )
  )
)
